# CAN.net
KiCad netlist of a schematic drawn in Altium Designer
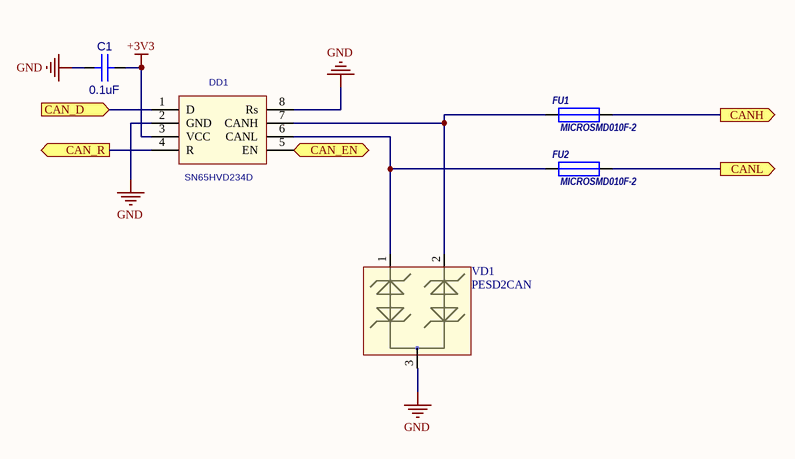
[diagram p0: CAN.SchDoc]

(export (version "E")
  (design (tool "Eeschema 10.0.6"))
  (components
    (comp (ref "C1")
      (value "0.1uF")
      (footprint "CC0603")
      (description "CC0603")
      (libsource (lib "gprs_modem_2") (part "CC0603"))
    )
    (comp (ref "DD1")
      (value "SN65HVD234D")
      (footprint "SO-8")
      (description "CAN Transceiver")
      (libsource (lib "gprs_modem_2") (part "SN65HVD234D"))
    )
    (comp (ref "FU1")
      (value "MICROSMD010F-2")
      (footprint "RC1210")
      (description "MICROSMD")
      (libsource (lib "gprs_modem_2") (part "MICROSMD"))
    )
    (comp (ref "FU2")
      (value "MICROSMD010F-2")
      (footprint "RC1210")
      (description "MICROSMD")
      (libsource (lib "gprs_modem_2") (part "MICROSMD"))
    )
    (comp (ref "VD1")
      (value "PESD2CAN")
      (footprint "SOT-23(123)")
      (description "TVS for CAN")
      (libsource (lib "gprs_modem_2") (part "PESD2CAN"))
    )
  )
  (nets
    (net (code "1") (name "+3V3") (class "Default")
      (node (ref "C1") (pin "2") (pinfunction "B_2") (pintype "passive"))
      (node (ref "DD1") (pin "3") (pinfunction "VCC_3") (pintype "passive"))
    )
    (net (code "2") (name "/CANH") (class "Default") (node (ref "FU1") (pin "2") (pintype "passive")))
    (net (code "3") (name "/CANL") (class "Default") (node (ref "FU2") (pin "2") (pintype "passive")))
    (net (code "4") (name "/CAN_D") (class "Default")
      (node (ref "DD1") (pin "1") (pinfunction "D_1") (pintype "passive"))
    )
    (net (code "5") (name "/CAN_EN") (class "Default")
      (node (ref "DD1") (pin "5") (pinfunction "EN_5") (pintype "passive"))
    )
    (net (code "6") (name "/CAN_R") (class "Default")
      (node (ref "DD1") (pin "4") (pinfunction "R_4") (pintype "passive"))
    )
    (net (code "7") (name "GND") (class "Default")
      (node (ref "C1") (pin "1") (pinfunction "A_1") (pintype "passive"))
      (node (ref "DD1") (pin "2") (pinfunction "GND_2") (pintype "passive"))
      (node (ref "DD1") (pin "8") (pinfunction "Rs_8") (pintype "passive"))
      (node (ref "VD1") (pin "3") (pinfunction "3_3") (pintype "passive"))
    )
    (net (code "8") (name "Net-(DD1-CANH)") (class "Default")
      (node (ref "DD1") (pin "7") (pinfunction "CANH_7") (pintype "passive"))
      (node (ref "FU1") (pin "1") (pintype "passive"))
      (node (ref "VD1") (pin "2") (pinfunction "2_2") (pintype "passive"))
    )
    (net (code "9") (name "Net-(DD1-CANL)") (class "Default")
      (node (ref "DD1") (pin "6") (pinfunction "CANL_6") (pintype "passive"))
      (node (ref "FU2") (pin "1") (pintype "passive"))
      (node (ref "VD1") (pin "1") (pinfunction "1_1") (pintype "passive"))
    )
  )
)
